# arduinoDccLight1_0.net
KiCad netlist of a schematic drawn in EAGLE
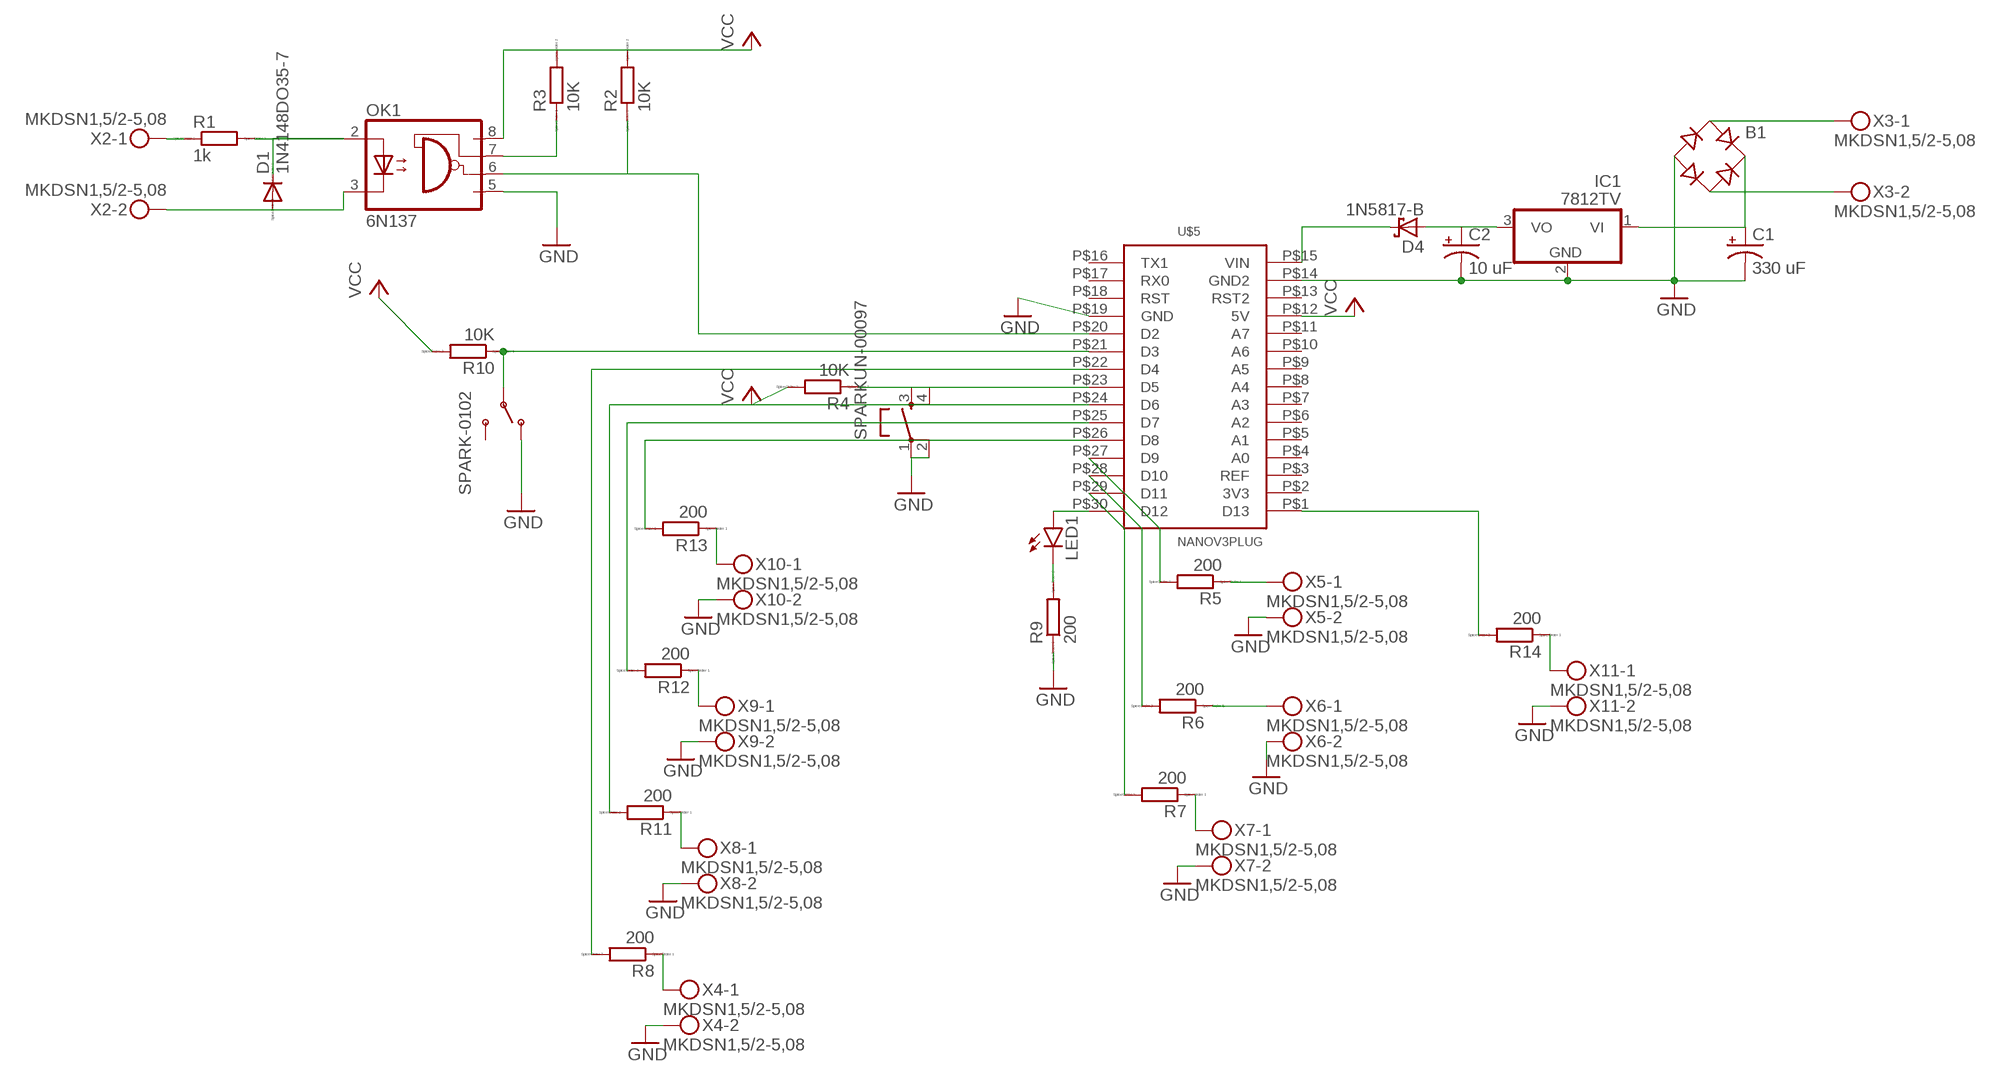
[diagram p0: schematic, sheet 1]

(export (version "E")
  (design (tool "Eeschema 10.0.6"))
  (components
    (comp (ref "B1")
      (value "RB1A")
      (footprint "eagle-import:RB1A")
      (libsource (lib "eagle-import") (part "RB1A"))
    )
    (comp (ref "C1")
      (value "330 uF")
      (footprint "eagle-import:CPOL-RADIAL-100UF-25V")
      (libsource (lib "eagle-import") (part "CAP_POLPTH1"))
    )
    (comp (ref "C2")
      (value "10 uF")
      (footprint "eagle-import:CPOL-RADIAL-100UF-25V")
      (libsource (lib "eagle-import") (part "CAP_POLPTH1"))
    )
    (comp (ref "D1")
      (value "1N4148DO35-7")
      (footprint "eagle-import:DO35-7")
      (libsource (lib "eagle-import") (part "1N4148DO35-7"))
    )
    (comp (ref "D4")
      (value "1N5817-B")
      (footprint "eagle-import:DO41-7.6")
      (libsource (lib "eagle-import") (part "1N5817-B"))
    )
    (comp (ref "IC1")
      (value "7812TV")
      (footprint "eagle-import:TO220V")
      (libsource (lib "eagle-import") (part "78TV12"))
    )
    (comp (ref "LED1")
      (value "LED3MM")
      (footprint "eagle-import:LED3MM")
      (libsource (lib "eagle-import") (part "LED3MM"))
    )
    (comp (ref "OK1")
      (value "6N137")
      (footprint "eagle-import:DIL08")
      (libsource (lib "eagle-import") (part "6N137"))
    )
    (comp (ref "R1")
      (value "1k")
      (footprint "eagle-import:0207_10")
      (libsource (lib "eagle-import") (part "R0207/10"))
    )
    (comp (ref "R2")
      (value "10K")
      (footprint "eagle-import:0207_10")
      (libsource (lib "eagle-import") (part "R0207/10"))
    )
    (comp (ref "R3")
      (value "10K")
      (footprint "eagle-import:0207_10")
      (libsource (lib "eagle-import") (part "R0207/10"))
    )
    (comp (ref "R4")
      (value "10K")
      (footprint "eagle-import:0207_10")
      (libsource (lib "eagle-import") (part "R0207/10"))
    )
    (comp (ref "R5")
      (value "200")
      (footprint "eagle-import:0207_10")
      (libsource (lib "eagle-import") (part "R0207/10"))
    )
    (comp (ref "R6")
      (value "200")
      (footprint "eagle-import:0207_10")
      (libsource (lib "eagle-import") (part "R0207/10"))
    )
    (comp (ref "R7")
      (value "200")
      (footprint "eagle-import:0207_10")
      (libsource (lib "eagle-import") (part "R0207/10"))
    )
    (comp (ref "R8")
      (value "200")
      (footprint "eagle-import:0207_10")
      (libsource (lib "eagle-import") (part "R0207/10"))
    )
    (comp (ref "R9")
      (value "200")
      (footprint "eagle-import:0204_7")
      (libsource (lib "eagle-import") (part "R0204/7"))
    )
    (comp (ref "R10")
      (value "10K")
      (footprint "eagle-import:0207_10")
      (libsource (lib "eagle-import") (part "R0207/10"))
    )
    (comp (ref "R11")
      (value "200")
      (footprint "eagle-import:0207_10")
      (libsource (lib "eagle-import") (part "R0207/10"))
    )
    (comp (ref "R12")
      (value "200")
      (footprint "eagle-import:0207_10")
      (libsource (lib "eagle-import") (part "R0207/10"))
    )
    (comp (ref "R13")
      (value "200")
      (footprint "eagle-import:0207_10")
      (libsource (lib "eagle-import") (part "R0207/10"))
    )
    (comp (ref "R14")
      (value "200")
      (footprint "eagle-import:0207_10")
      (libsource (lib "eagle-import") (part "R0207/10"))
    )
    (comp (ref "SPARK-0102")
      (value "SWITCH-SPDTPTH")
      (footprint "eagle-import:SWITCH-SPDT")
      (libsource (lib "eagle-import") (part "SWITCH-SPDTPTH"))
    )
    (comp (ref "SPARKUN-00097")
      (value "TAC_SWITCHPTH")
      (footprint "eagle-import:TACTILE-PTH")
      (libsource (lib "eagle-import") (part "TAC_SWITCHPTH"))
    )
    (comp (ref "U$5")
      (value "NANOV3PLUG")
      (footprint "eagle-import:HEADER15-2")
      (libsource (lib "eagle-import") (part "NANOV3PLUG"))
    )
    (comp (ref "X2")
      (value "MKDSN1,5/2-5,08")
      (footprint "eagle-import:MKDSN1,5_2-5,08")
      (libsource (lib "eagle-import") (part "MKDSN1,5/2-5,08"))
    )
    (comp (ref "X3")
      (value "MKDSN1,5/2-5,08")
      (footprint "eagle-import:MKDSN1,5_2-5,08")
      (libsource (lib "eagle-import") (part "MKDSN1,5/2-5,08"))
    )
    (comp (ref "X4")
      (value "MKDSN1,5/2-5,08")
      (footprint "eagle-import:MKDSN1,5_2-5,08")
      (libsource (lib "eagle-import") (part "MKDSN1,5/2-5,08"))
    )
    (comp (ref "X5")
      (value "MKDSN1,5/2-5,08")
      (footprint "eagle-import:MKDSN1,5_2-5,08")
      (libsource (lib "eagle-import") (part "MKDSN1,5/2-5,08"))
    )
    (comp (ref "X6")
      (value "MKDSN1,5/2-5,08")
      (footprint "eagle-import:MKDSN1,5_2-5,08")
      (libsource (lib "eagle-import") (part "MKDSN1,5/2-5,08"))
    )
    (comp (ref "X7")
      (value "MKDSN1,5/2-5,08")
      (footprint "eagle-import:MKDSN1,5_2-5,08")
      (libsource (lib "eagle-import") (part "MKDSN1,5/2-5,08"))
    )
    (comp (ref "X8")
      (value "MKDSN1,5/2-5,08")
      (footprint "eagle-import:MKDSN1,5_2-5,08")
      (libsource (lib "eagle-import") (part "MKDSN1,5/2-5,08"))
    )
    (comp (ref "X9")
      (value "MKDSN1,5/2-5,08")
      (footprint "eagle-import:MKDSN1,5_2-5,08")
      (libsource (lib "eagle-import") (part "MKDSN1,5/2-5,08"))
    )
    (comp (ref "X10")
      (value "MKDSN1,5/2-5,08")
      (footprint "eagle-import:MKDSN1,5_2-5,08")
      (libsource (lib "eagle-import") (part "MKDSN1,5/2-5,08"))
    )
    (comp (ref "X11")
      (value "MKDSN1,5/2-5,08")
      (footprint "eagle-import:MKDSN1,5_2-5,08")
      (libsource (lib "eagle-import") (part "MKDSN1,5/2-5,08"))
    )
  )
  (nets
    (net (code "1") (name "GND") (class "Default")
      (node (ref "B1") (pin "-") (pinfunction "-_-") (pintype "passive"))
      (node (ref "C1") (pin "2") (pinfunction "-_2") (pintype "passive"))
      (node (ref "C2") (pin "2") (pinfunction "-_2") (pintype "passive"))
      (node (ref "IC1") (pin "2") (pinfunction "GND_2") (pintype "passive"))
      (node (ref "OK1") (pin "5") (pinfunction "GND_5") (pintype "passive"))
      (node (ref "R9") (pin "1") (pinfunction "1_1") (pintype "passive"))
      (node (ref "SPARK-0102") (pin "1") (pinfunction "O_1") (pintype "passive"))
      (node (ref "SPARKUN-00097") (pin "1") (pinfunction "1_1") (pintype "passive"))
      (node (ref "SPARKUN-00097") (pin "2") (pinfunction "2_2") (pintype "passive"))
      (node (ref "U$5") (pin "P$14") (pinfunction "GND2_P$14") (pintype "bidirectional"))
      (node (ref "U$5") (pin "P$19") (pinfunction "GND_P$19") (pintype "bidirectional"))
      (node (ref "X10") (pin "2") (pinfunction "KL_2") (pintype "passive"))
      (node (ref "X11") (pin "2") (pinfunction "KL_2") (pintype "passive"))
      (node (ref "X4") (pin "2") (pinfunction "KL_2") (pintype "passive"))
      (node (ref "X5") (pin "2") (pinfunction "KL_2") (pintype "passive"))
      (node (ref "X6") (pin "2") (pinfunction "KL_2") (pintype "passive"))
      (node (ref "X7") (pin "2") (pinfunction "KL_2") (pintype "passive"))
      (node (ref "X8") (pin "2") (pinfunction "KL_2") (pintype "passive"))
      (node (ref "X9") (pin "2") (pinfunction "KL_2") (pintype "passive"))
    )
    (net (code "2") (name "Net-(C1-+)") (class "Default")
      (node (ref "B1") (pin "+") (pinfunction "+_+") (pintype "passive"))
      (node (ref "C1") (pin "1") (pinfunction "+_1") (pintype "passive"))
      (node (ref "IC1") (pin "1") (pinfunction "VI_1") (pintype "input"))
    )
    (net (code "3") (name "Net-(C2-+)") (class "Default")
      (node (ref "C2") (pin "1") (pinfunction "+_1") (pintype "passive"))
      (node (ref "D4") (pin "A") (pinfunction "A_A") (pintype "passive"))
      (node (ref "IC1") (pin "3") (pinfunction "VO_3") (pintype "passive"))
    )
    (net (code "4") (name "Net-(LED1-C)") (class "Default")
      (node (ref "LED1") (pin "K") (pinfunction "C_K") (pintype "passive"))
      (node (ref "R9") (pin "2") (pinfunction "2_2") (pintype "passive"))
    )
    (net (code "5") (name "Net-(OK1-A)") (class "Default")
      (node (ref "D1") (pin "C") (pinfunction "C_C") (pintype "passive"))
      (node (ref "OK1") (pin "2") (pinfunction "A_2") (pintype "passive"))
      (node (ref "R1") (pin "2") (pinfunction "2_2") (pintype "passive"))
    )
    (net (code "6") (name "Net-(OK1-C)") (class "Default")
      (node (ref "D1") (pin "A") (pinfunction "A_A") (pintype "passive"))
      (node (ref "OK1") (pin "3") (pinfunction "C_3") (pintype "passive"))
      (node (ref "X2") (pin "2") (pinfunction "KL_2") (pintype "passive"))
    )
    (net (code "7") (name "Net-(OK1-VE)") (class "Default")
      (node (ref "OK1") (pin "7") (pinfunction "VE_7") (pintype "passive"))
      (node (ref "R3") (pin "1") (pinfunction "1_1") (pintype "passive"))
    )
    (net (code "8") (name "Net-(OK1-VO)") (class "Default")
      (node (ref "OK1") (pin "6") (pinfunction "VO_6") (pintype "passive"))
      (node (ref "R2") (pin "1") (pinfunction "1_1") (pintype "passive"))
      (node (ref "U$5") (pin "P$20") (pinfunction "D2_P$20") (pintype "bidirectional"))
    )
    (net (code "9") (name "Net-(SPARK-0102-P)") (class "Default")
      (node (ref "R10") (pin "1") (pinfunction "1_1") (pintype "passive"))
      (node (ref "SPARK-0102") (pin "2") (pinfunction "P_2") (pintype "passive"))
      (node (ref "U$5") (pin "P$21") (pinfunction "D3_P$21") (pintype "bidirectional"))
    )
    (net (code "10") (name "Net-(U$5-D4)") (class "Default")
      (node (ref "R8") (pin "2") (pinfunction "2_2") (pintype "passive"))
      (node (ref "U$5") (pin "P$22") (pinfunction "D4_P$22") (pintype "bidirectional"))
    )
    (net (code "11") (name "Net-(U$5-D5)") (class "Default")
      (node (ref "R4") (pin "1") (pinfunction "1_1") (pintype "passive"))
      (node (ref "SPARKUN-00097") (pin "3") (pinfunction "3_3") (pintype "passive"))
      (node (ref "SPARKUN-00097") (pin "4") (pinfunction "4_4") (pintype "passive"))
      (node (ref "U$5") (pin "P$23") (pinfunction "D5_P$23") (pintype "bidirectional"))
    )
    (net (code "12") (name "Net-(U$5-D6)") (class "Default")
      (node (ref "R11") (pin "2") (pinfunction "2_2") (pintype "passive"))
      (node (ref "U$5") (pin "P$24") (pinfunction "D6_P$24") (pintype "bidirectional"))
    )
    (net (code "13") (name "Net-(U$5-D7)") (class "Default")
      (node (ref "R12") (pin "2") (pinfunction "2_2") (pintype "passive"))
      (node (ref "U$5") (pin "P$25") (pinfunction "D7_P$25") (pintype "bidirectional"))
    )
    (net (code "14") (name "Net-(U$5-D8)") (class "Default")
      (node (ref "R13") (pin "2") (pinfunction "2_2") (pintype "passive"))
      (node (ref "U$5") (pin "P$26") (pinfunction "D8_P$26") (pintype "bidirectional"))
    )
    (net (code "15") (name "Net-(U$5-D9)") (class "Default")
      (node (ref "R5") (pin "2") (pinfunction "2_2") (pintype "passive"))
      (node (ref "U$5") (pin "P$27") (pinfunction "D9_P$27") (pintype "bidirectional"))
    )
    (net (code "16") (name "Net-(U$5-D10)") (class "Default")
      (node (ref "R6") (pin "2") (pinfunction "2_2") (pintype "passive"))
      (node (ref "U$5") (pin "P$28") (pinfunction "D10_P$28") (pintype "bidirectional"))
    )
    (net (code "17") (name "Net-(U$5-D11)") (class "Default")
      (node (ref "R7") (pin "2") (pinfunction "2_2") (pintype "passive"))
      (node (ref "U$5") (pin "P$29") (pinfunction "D11_P$29") (pintype "bidirectional"))
    )
    (net (code "18") (name "Net-(U$5-D12)") (class "Default")
      (node (ref "LED1") (pin "A") (pinfunction "A_A") (pintype "passive"))
      (node (ref "U$5") (pin "P$30") (pinfunction "D12_P$30") (pintype "bidirectional"))
    )
    (net (code "19") (name "Net-(U$5-D13)") (class "Default")
      (node (ref "R14") (pin "2") (pinfunction "2_2") (pintype "passive"))
      (node (ref "U$5") (pin "P$1") (pinfunction "D13_P$1") (pintype "bidirectional"))
    )
    (net (code "20") (name "Net-(U$5-VIN)") (class "Default")
      (node (ref "D4") (pin "C") (pinfunction "C_C") (pintype "passive"))
      (node (ref "U$5") (pin "P$15") (pinfunction "VIN_P$15") (pintype "bidirectional"))
    )
    (net (code "21") (name "Net-(X2A-KL)") (class "Default")
      (node (ref "R1") (pin "1") (pinfunction "1_1") (pintype "passive"))
      (node (ref "X2") (pin "1") (pinfunction "KL_1") (pintype "passive"))
    )
    (net (code "22") (name "Net-(X3A-KL)") (class "Default")
      (node (ref "B1") (pin "AC1") (pinfunction "AC1_AC1") (pintype "passive"))
      (node (ref "X3") (pin "1") (pinfunction "KL_1") (pintype "passive"))
    )
    (net (code "23") (name "Net-(X3B-KL)") (class "Default")
      (node (ref "B1") (pin "AC2") (pinfunction "AC2_AC2") (pintype "passive"))
      (node (ref "X3") (pin "2") (pinfunction "KL_2") (pintype "passive"))
    )
    (net (code "24") (name "Net-(X4A-KL)") (class "Default")
      (node (ref "R8") (pin "1") (pinfunction "1_1") (pintype "passive"))
      (node (ref "X4") (pin "1") (pinfunction "KL_1") (pintype "passive"))
    )
    (net (code "25") (name "Net-(X5A-KL)") (class "Default")
      (node (ref "R5") (pin "1") (pinfunction "1_1") (pintype "passive"))
      (node (ref "X5") (pin "1") (pinfunction "KL_1") (pintype "passive"))
    )
    (net (code "26") (name "Net-(X6A-KL)") (class "Default")
      (node (ref "R6") (pin "1") (pinfunction "1_1") (pintype "passive"))
      (node (ref "X6") (pin "1") (pinfunction "KL_1") (pintype "passive"))
    )
    (net (code "27") (name "Net-(X7A-KL)") (class "Default")
      (node (ref "R7") (pin "1") (pinfunction "1_1") (pintype "passive"))
      (node (ref "X7") (pin "1") (pinfunction "KL_1") (pintype "passive"))
    )
    (net (code "28") (name "Net-(X8A-KL)") (class "Default")
      (node (ref "R11") (pin "1") (pinfunction "1_1") (pintype "passive"))
      (node (ref "X8") (pin "1") (pinfunction "KL_1") (pintype "passive"))
    )
    (net (code "29") (name "Net-(X9A-KL)") (class "Default")
      (node (ref "R12") (pin "1") (pinfunction "1_1") (pintype "passive"))
      (node (ref "X9") (pin "1") (pinfunction "KL_1") (pintype "passive"))
    )
    (net (code "30") (name "Net-(X10A-KL)") (class "Default")
      (node (ref "R13") (pin "1") (pinfunction "1_1") (pintype "passive"))
      (node (ref "X10") (pin "1") (pinfunction "KL_1") (pintype "passive"))
    )
    (net (code "31") (name "Net-(X11A-KL)") (class "Default")
      (node (ref "R14") (pin "1") (pinfunction "1_1") (pintype "passive"))
      (node (ref "X11") (pin "1") (pinfunction "KL_1") (pintype "passive"))
    )
    (net (code "32") (name "VCC") (class "Default")
      (node (ref "OK1") (pin "8") (pinfunction "VCC_8") (pintype "passive"))
      (node (ref "R10") (pin "2") (pinfunction "2_2") (pintype "passive"))
      (node (ref "R2") (pin "2") (pinfunction "2_2") (pintype "passive"))
      (node (ref "R3") (pin "2") (pinfunction "2_2") (pintype "passive"))
      (node (ref "R4") (pin "2") (pinfunction "2_2") (pintype "passive"))
      (node (ref "U$5") (pin "P$12") (pinfunction "5V_P$12") (pintype "bidirectional"))
    )
    (net (code "33") (name "unconnected-(SPARK-0102-S-Pad3)") (class "Default")
      (node (ref "SPARK-0102") (pin "3") (pinfunction "S_3") (pintype "passive"))
    )
    (net (code "34") (name "unconnected-(U$5-3V3-PadP$2)") (class "Default")
      (node (ref "U$5") (pin "P$2") (pinfunction "3V3_P$2") (pintype "bidirectional"))
    )
    (net (code "35") (name "unconnected-(U$5-A0-PadP$4)") (class "Default")
      (node (ref "U$5") (pin "P$4") (pinfunction "A0_P$4") (pintype "bidirectional"))
    )
    (net (code "36") (name "unconnected-(U$5-A1-PadP$5)") (class "Default")
      (node (ref "U$5") (pin "P$5") (pinfunction "A1_P$5") (pintype "bidirectional"))
    )
    (net (code "37") (name "unconnected-(U$5-A2-PadP$6)") (class "Default")
      (node (ref "U$5") (pin "P$6") (pinfunction "A2_P$6") (pintype "bidirectional"))
    )
    (net (code "38") (name "unconnected-(U$5-A3-PadP$7)") (class "Default")
      (node (ref "U$5") (pin "P$7") (pinfunction "A3_P$7") (pintype "bidirectional"))
    )
    (net (code "39") (name "unconnected-(U$5-A4-PadP$8)") (class "Default")
      (node (ref "U$5") (pin "P$8") (pinfunction "A4_P$8") (pintype "bidirectional"))
    )
    (net (code "40") (name "unconnected-(U$5-A5-PadP$9)") (class "Default")
      (node (ref "U$5") (pin "P$9") (pinfunction "A5_P$9") (pintype "bidirectional"))
    )
    (net (code "41") (name "unconnected-(U$5-A6-PadP$10)") (class "Default")
      (node (ref "U$5") (pin "P$10") (pinfunction "A6_P$10") (pintype "bidirectional"))
    )
    (net (code "42") (name "unconnected-(U$5-A7-PadP$11)") (class "Default")
      (node (ref "U$5") (pin "P$11") (pinfunction "A7_P$11") (pintype "bidirectional"))
    )
    (net (code "43") (name "unconnected-(U$5-REF-PadP$3)") (class "Default")
      (node (ref "U$5") (pin "P$3") (pinfunction "REF_P$3") (pintype "bidirectional"))
    )
    (net (code "44") (name "unconnected-(U$5-RST-PadP$18)") (class "Default")
      (node (ref "U$5") (pin "P$18") (pinfunction "RST_P$18") (pintype "bidirectional"))
    )
    (net (code "45") (name "unconnected-(U$5-RST2-PadP$13)") (class "Default")
      (node (ref "U$5") (pin "P$13") (pinfunction "RST2_P$13") (pintype "bidirectional"))
    )
    (net (code "46") (name "unconnected-(U$5-RX0-PadP$17)") (class "Default")
      (node (ref "U$5") (pin "P$17") (pinfunction "RX0_P$17") (pintype "bidirectional"))
    )
    (net (code "47") (name "unconnected-(U$5-TX1-PadP$16)") (class "Default")
      (node (ref "U$5") (pin "P$16") (pinfunction "TX1_P$16") (pintype "bidirectional"))
    )
  )
)
